# Power.net
KiCad netlist of a schematic drawn in Altium Designer
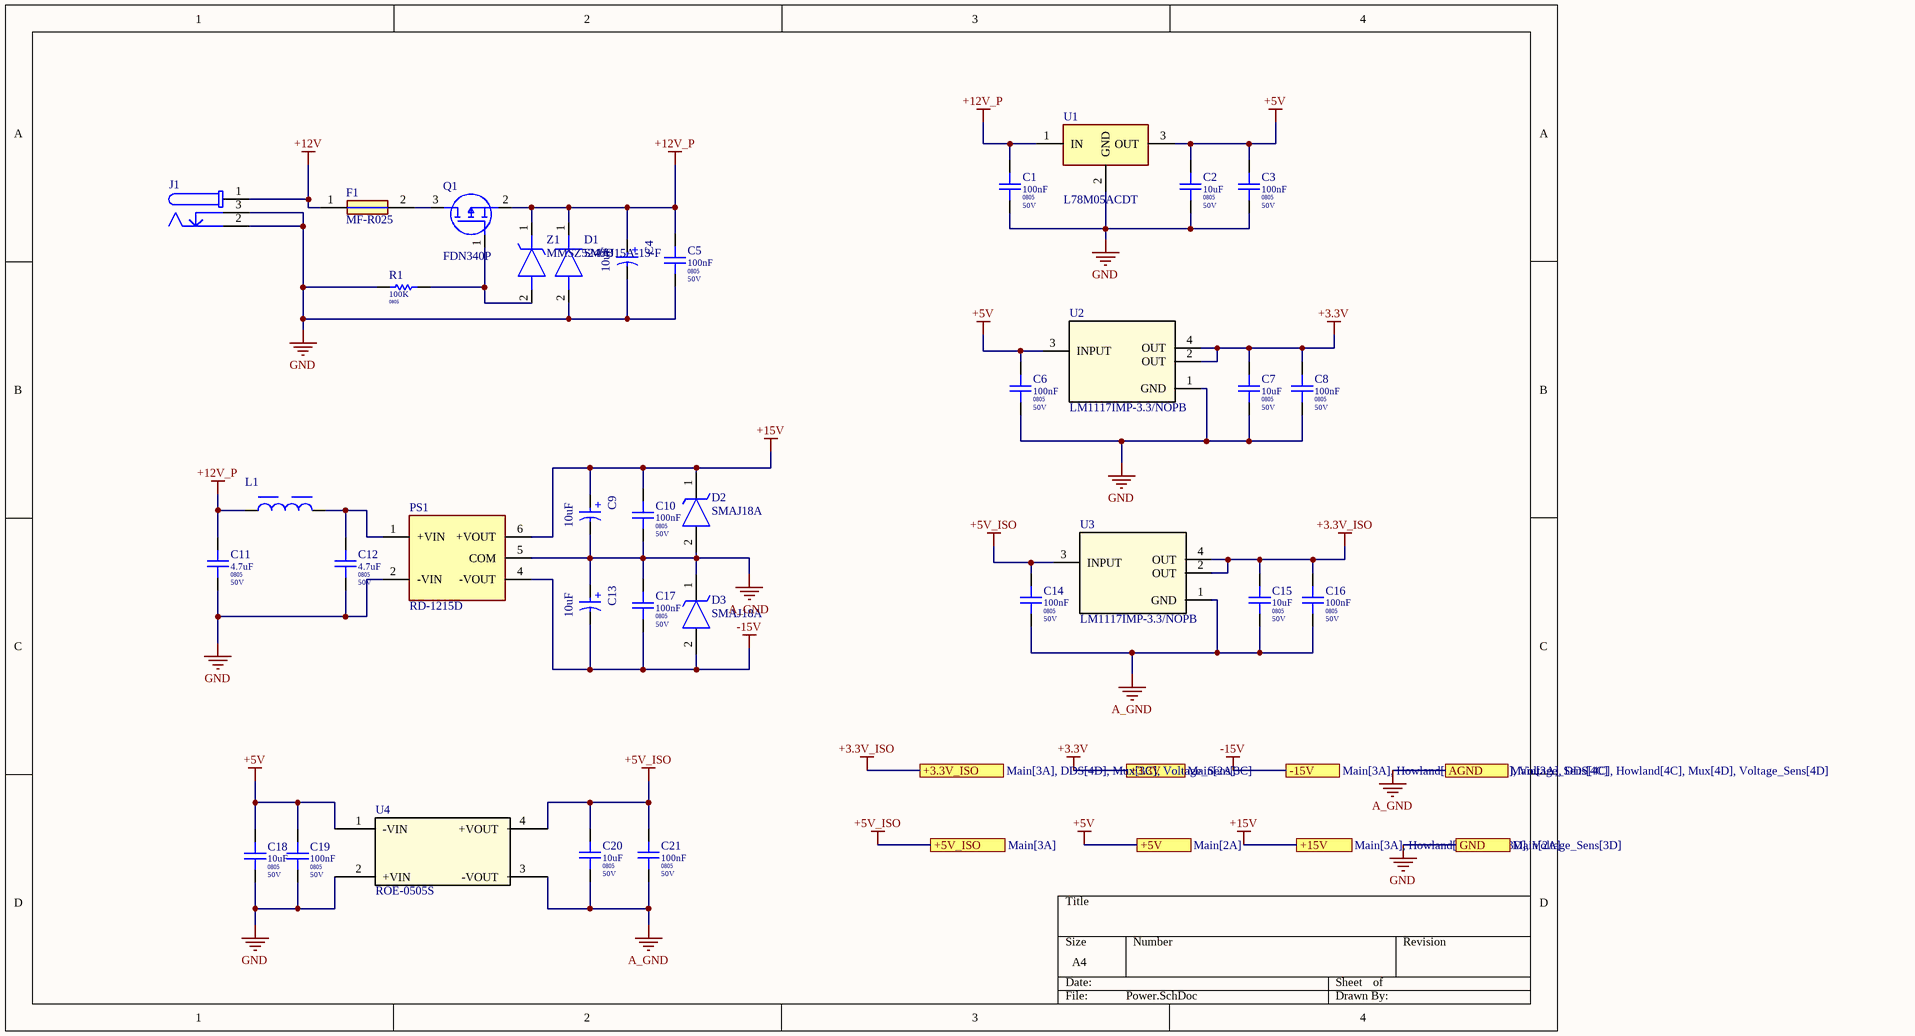
[diagram p0: Power.SchDoc]

(export (version "E")
  (design (tool "Eeschema 10.0.6"))
  (components
    (comp (ref "C1")
      (value "100nF")
      (footprint "CAPC 0805")
      (description "Capacitor Ceramic 100nF 50V 0805")
      (fields
        (field (name "TOLERANCE") "%10")
        (field (name "PACKAGE / CASE") "0805")
        (field (name "VOLTAGE") "50V")
        (field (name "PART NUMBER") "CAPC0572")
      )
      (libsource (lib "Aesk Database Library") (part "NPCapacitor"))
    )
    (comp (ref "C2")
      (value "10uF")
      (footprint "CAPC 0805")
      (description "Capacitor Ceramic 10uF 50V 0805")
      (fields
        (field (name "TOLERANCE") "%10")
        (field (name "PACKAGE / CASE") "0805")
        (field (name "VOLTAGE") "50V")
        (field (name "PART NUMBER") "CAPC0588")
      )
      (libsource (lib "Aesk Database Library") (part "NPCapacitor"))
    )
    (comp (ref "C3")
      (value "100nF")
      (footprint "CAPC 0805")
      (description "Capacitor Ceramic 100nF 50V 0805")
      (fields
        (field (name "TOLERANCE") "%10")
        (field (name "PACKAGE / CASE") "0805")
        (field (name "VOLTAGE") "50V")
        (field (name "PART NUMBER") "CAPC0572")
      )
      (libsource (lib "Aesk Database Library") (part "NPCapacitor"))
    )
    (comp (ref "C4")
      (value "10uF")
      (footprint "WCAP-ATG5_D5H11")
      (description "WCAP-ATG5 Aluminum Electrolytic Capacitor, Radial, THT, D5 x H11mm, 10µF, 35V")
      (fields
        (field (name "MANUFACTURER PART NUMBER") "860020572003")
        (field (name "MANUFACTURER") "Wurth Elektronik")
      )
      (libsource (lib "WE - Passive Components") (part "Capacitor_Polarized"))
    )
    (comp (ref "C5")
      (value "100nF")
      (footprint "CAPC 0805")
      (description "Capacitor Ceramic 100nF 50V 0805")
      (fields
        (field (name "TOLERANCE") "%10")
        (field (name "PACKAGE / CASE") "0805")
        (field (name "VOLTAGE") "50V")
        (field (name "PART NUMBER") "CAPC0572")
      )
      (libsource (lib "Aesk Database Library") (part "NPCapacitor"))
    )
    (comp (ref "C6")
      (value "100nF")
      (footprint "CAPC 0805")
      (description "Capacitor Ceramic 100nF 50V 0805")
      (fields
        (field (name "TOLERANCE") "%10")
        (field (name "PACKAGE / CASE") "0805")
        (field (name "VOLTAGE") "50V")
        (field (name "PART NUMBER") "CAPC0572")
      )
      (libsource (lib "Aesk Database Library") (part "NPCapacitor"))
    )
    (comp (ref "C7")
      (value "10uF")
      (footprint "CAPC 0805")
      (description "Capacitor Ceramic 10uF 50V 0805")
      (fields
        (field (name "TOLERANCE") "%10")
        (field (name "PACKAGE / CASE") "0805")
        (field (name "VOLTAGE") "50V")
        (field (name "PART NUMBER") "CAPC0588")
      )
      (libsource (lib "Aesk Database Library") (part "NPCapacitor"))
    )
    (comp (ref "C8")
      (value "100nF")
      (footprint "CAPC 0805")
      (description "Capacitor Ceramic 100nF 50V 0805")
      (fields
        (field (name "TOLERANCE") "%10")
        (field (name "PACKAGE / CASE") "0805")
        (field (name "VOLTAGE") "50V")
        (field (name "PART NUMBER") "CAPC0572")
      )
      (libsource (lib "Aesk Database Library") (part "NPCapacitor"))
    )
    (comp (ref "C9")
      (value "10uF")
      (footprint "WCAP-ATG5_D5H11")
      (description "WCAP-ATG5 Aluminum Electrolytic Capacitor, Radial, THT, D5 x H11mm, 10µF, 35V")
      (fields
        (field (name "MANUFACTURER PART NUMBER") "860020572003")
        (field (name "MANUFACTURER") "Wurth Elektronik")
      )
      (libsource (lib "WE - Passive Components") (part "Capacitor_Polarized"))
    )
    (comp (ref "C10")
      (value "100nF")
      (footprint "CAPC 0805")
      (description "Capacitor Ceramic 100nF 50V 0805")
      (fields
        (field (name "TOLERANCE") "%10")
        (field (name "PACKAGE / CASE") "0805")
        (field (name "VOLTAGE") "50V")
        (field (name "PART NUMBER") "CAPC0572")
      )
      (libsource (lib "Aesk Database Library") (part "NPCapacitor"))
    )
    (comp (ref "C11")
      (value "4.7uF")
      (footprint "CAPC 0805")
      (description "Capacitor Ceramic 4.7uF 50V 0805")
      (fields
        (field (name "TOLERANCE") "%10")
        (field (name "PACKAGE / CASE") "0805")
        (field (name "VOLTAGE") "50V")
        (field (name "PART NUMBER") "CAPC0584")
      )
      (libsource (lib "Aesk Database Library") (part "NPCapacitor"))
    )
    (comp (ref "C12")
      (value "4.7uF")
      (footprint "CAPC 0805")
      (description "Capacitor Ceramic 4.7uF 50V 0805")
      (fields
        (field (name "TOLERANCE") "%10")
        (field (name "PACKAGE / CASE") "0805")
        (field (name "VOLTAGE") "50V")
        (field (name "PART NUMBER") "CAPC0584")
      )
      (libsource (lib "Aesk Database Library") (part "NPCapacitor"))
    )
    (comp (ref "C13")
      (value "10uF")
      (footprint "WCAP-ATG5_D5H11")
      (description "WCAP-ATG5 Aluminum Electrolytic Capacitor, Radial, THT, D5 x H11mm, 10µF, 35V")
      (fields
        (field (name "MANUFACTURER PART NUMBER") "860020572003")
        (field (name "MANUFACTURER") "Wurth Elektronik")
      )
      (libsource (lib "WE - Passive Components") (part "Capacitor_Polarized"))
    )
    (comp (ref "C14")
      (value "100nF")
      (footprint "CAPC 0805")
      (description "Capacitor Ceramic 100nF 50V 0805")
      (fields
        (field (name "TOLERANCE") "%10")
        (field (name "PACKAGE / CASE") "0805")
        (field (name "VOLTAGE") "50V")
        (field (name "PART NUMBER") "CAPC0572")
      )
      (libsource (lib "Aesk Database Library") (part "NPCapacitor"))
    )
    (comp (ref "C15")
      (value "10uF")
      (footprint "CAPC 0805")
      (description "Capacitor Ceramic 10uF 50V 0805")
      (fields
        (field (name "TOLERANCE") "%10")
        (field (name "PACKAGE / CASE") "0805")
        (field (name "VOLTAGE") "50V")
        (field (name "PART NUMBER") "CAPC0588")
      )
      (libsource (lib "Aesk Database Library") (part "NPCapacitor"))
    )
    (comp (ref "C16")
      (value "100nF")
      (footprint "CAPC 0805")
      (description "Capacitor Ceramic 100nF 50V 0805")
      (fields
        (field (name "TOLERANCE") "%10")
        (field (name "PACKAGE / CASE") "0805")
        (field (name "VOLTAGE") "50V")
        (field (name "PART NUMBER") "CAPC0572")
      )
      (libsource (lib "Aesk Database Library") (part "NPCapacitor"))
    )
    (comp (ref "C17")
      (value "100nF")
      (footprint "CAPC 0805")
      (description "Capacitor Ceramic 100nF 50V 0805")
      (fields
        (field (name "TOLERANCE") "%10")
        (field (name "PACKAGE / CASE") "0805")
        (field (name "VOLTAGE") "50V")
        (field (name "PART NUMBER") "CAPC0572")
      )
      (libsource (lib "Aesk Database Library") (part "NPCapacitor"))
    )
    (comp (ref "C18")
      (value "10uF")
      (footprint "CAPC 0805")
      (description "Capacitor Ceramic 10uF 50V 0805")
      (fields
        (field (name "TOLERANCE") "%10")
        (field (name "PACKAGE / CASE") "0805")
        (field (name "VOLTAGE") "50V")
        (field (name "PART NUMBER") "CAPC0588")
      )
      (libsource (lib "Aesk Database Library") (part "NPCapacitor"))
    )
    (comp (ref "C19")
      (value "100nF")
      (footprint "CAPC 0805")
      (description "Capacitor Ceramic 100nF 50V 0805")
      (fields
        (field (name "TOLERANCE") "%10")
        (field (name "PACKAGE / CASE") "0805")
        (field (name "VOLTAGE") "50V")
        (field (name "PART NUMBER") "CAPC0572")
      )
      (libsource (lib "Aesk Database Library") (part "NPCapacitor"))
    )
    (comp (ref "C20")
      (value "10uF")
      (footprint "CAPC 0805")
      (description "Capacitor Ceramic 10uF 50V 0805")
      (fields
        (field (name "TOLERANCE") "%10")
        (field (name "PACKAGE / CASE") "0805")
        (field (name "VOLTAGE") "50V")
        (field (name "PART NUMBER") "CAPC0588")
      )
      (libsource (lib "Aesk Database Library") (part "NPCapacitor"))
    )
    (comp (ref "C21")
      (value "100nF")
      (footprint "CAPC 0805")
      (description "Capacitor Ceramic 100nF 50V 0805")
      (fields
        (field (name "TOLERANCE") "%10")
        (field (name "PACKAGE / CASE") "0805")
        (field (name "VOLTAGE") "50V")
        (field (name "PART NUMBER") "CAPC0572")
      )
      (libsource (lib "Aesk Database Library") (part "NPCapacitor"))
    )
    (comp (ref "D1")
      (value "SMAJ15A-13-F")
      (footprint "SamacSys:DIOM5226X240N")
      (description "Diode")
      (fields (field (name "MOUSER PART NUMBER") "621-SMAJ15A-13-F"))
      (libsource (lib "Schlib1") (part "SMAJ15A-13-F"))
    )
    (comp (ref "D2")
      (value "SMAJ18A")
      (footprint "SamacSys:DIOM5026X229N")
      (description "TVS Diode (Uni-directional)")
      (fields (field (name "MOUSER PART NUMBER") "576-SMAJ18A"))
      (libsource (lib "Schlib1") (part "SMAJ18A"))
    )
    (comp (ref "D3")
      (value "SMAJ18A")
      (footprint "SamacSys:DIOM5026X229N")
      (description "TVS Diode (Uni-directional)")
      (fields (field (name "MOUSER PART NUMBER") "576-SMAJ18A"))
      (libsource (lib "Schlib1") (part "SMAJ18A"))
    )
    (comp (ref "F1")
      (value "MF-R025")
      (footprint "SamacSys:MFR025")
      (description "Fuse")
      (fields (field (name "MOUSER PART NUMBER") "652-MFR025"))
      (libsource (lib "Schlib1") (part "MF-R025"))
    )
    (comp (ref "J1")
      (value "694106301002")
      (footprint "694106301002")
      (description "WR-DC Power Jack, THT, Right Angled, Center Pin 2mm, 5A, 30V (DC)")
      (fields (field (name "MANUFACTURER") "Wurth Elektronik"))
      (libsource (lib "WE - Electromechanical Components") (part "DC Power Jack_Switch On Pin 2"))
    )
    (comp (ref "L1")
      (value "10uH, 0.74A")
      (footprint "WE-TPC_3816")
      (description "WE-TPC SMT Tiny Power Inductor, size 3816, 10uH, 0.74A, 185mOhm")
      (fields
        (field (name "MANUFACTURER PART NUMBER") "744031100")
        (field (name "MANUFACTURER") "Wurth Elektronik")
      )
      (libsource (lib "WE - Passive Components") (part "Inductor - 3"))
    )
    (comp (ref "PS1")
      (value "RD-1215D")
      (footprint "SamacSys:RD1215D")
      (description "Power Supply")
      (fields (field (name "MOUSER PART NUMBER") "919-RD-1215D"))
      (libsource (lib "Schlib1") (part "RD-1215D"))
    )
    (comp (ref "Q1")
      (value "FDN340P")
      (footprint "SamacSys:SOT95P237X112-3N")
      (description "MOSFET (P-Channel)")
      (fields (field (name "MOUSER PART NUMBER") "512-FDN340P"))
      (libsource (lib "Schlib1") (part "FDN340P"))
    )
    (comp (ref "R1")
      (value "100K")
      (footprint "RESC 0805")
      (description "100K 0805")
      (fields
        (field (name "TOLERANCE") "%5")
        (field (name "POWER") "1/10W")
        (field (name "PACKAGE / CASE") "0805")
      )
      (libsource (lib "Aesk Database Library") (part "Resistor"))
    )
    (comp (ref "U1")
      (value "L78M05ACDT")
      (footprint "SamacSys:L78M05ACDT")
      (description "Integrated Circuit")
      (fields (field (name "MOUSER PART NUMBER") "511-L78M05ACDT"))
      (libsource (lib "Schlib1") (part "L78M05ACDT"))
    )
    (comp (ref "U2")
      (value "LM1117IMP-3.3/NOPB")
      (footprint "DCY0004A_M")
      (description "800-mA 15-V linear voltage regulator 4-SOT-223 -40 to 125")
      (fields (field (name "COPYRIGHT") "Copyright (C) 2025 Ultra Librarian. All rights reserved."))
      (libsource (lib "Schlib1") (part "LM1117IMP-3.3NOPB"))
    )
    (comp (ref "U3")
      (value "LM1117IMP-3.3/NOPB")
      (footprint "DCY0004A_M")
      (description "800-mA 15-V linear voltage regulator 4-SOT-223 -40 to 125")
      (fields (field (name "COPYRIGHT") "Copyright (C) 2025 Ultra Librarian. All rights reserved."))
      (libsource (lib "Schlib1") (part "LM1117IMP-3.3NOPB"))
    )
    (comp (ref "U4")
      (value "ROE-0505S")
      (footprint "ROE_RCP")
      (description "Description")
      (fields (field (name "COPYRIGHT") "Copyright (C) 2026 Ultra Librarian. All rights reserved."))
      (libsource (lib "Schlib1") (part "ROE-0505S"))
    )
    (comp (ref "Z1")
      (value "MMSZ5240B")
      (footprint "SamacSys:SOD3816X128N")
      (description "Zener Diode")
      (fields (field (name "MOUSER PART NUMBER") "512-MMSZ5240B"))
      (libsource (lib "Schlib1") (part "MMSZ5240B"))
    )
  )
  (nets
    (net (code "1") (name "+3.3V") (class "Default")
      (node (ref "C7") (pin "2") (pinfunction "2_2") (pintype "passive"))
      (node (ref "C8") (pin "2") (pinfunction "2_2") (pintype "passive"))
      (node (ref "U2") (pin "2") (pinfunction "OUT_2") (pintype "power_in"))
      (node (ref "U2") (pin "4") (pinfunction "OUT_4") (pintype "power_in"))
    )
    (net (code "2") (name "+3.3V_ISO") (class "Default")
      (node (ref "C15") (pin "2") (pinfunction "2_2") (pintype "passive"))
      (node (ref "C16") (pin "2") (pinfunction "2_2") (pintype "passive"))
      (node (ref "U3") (pin "2") (pinfunction "OUT_2") (pintype "power_in"))
      (node (ref "U3") (pin "4") (pinfunction "OUT_4") (pintype "power_in"))
    )
    (net (code "3") (name "+5V") (class "Default")
      (node (ref "C18") (pin "2") (pinfunction "2_2") (pintype "passive"))
      (node (ref "C19") (pin "2") (pinfunction "2_2") (pintype "passive"))
      (node (ref "C2") (pin "2") (pinfunction "2_2") (pintype "passive"))
      (node (ref "C3") (pin "2") (pinfunction "2_2") (pintype "passive"))
      (node (ref "C6") (pin "2") (pinfunction "2_2") (pintype "passive"))
      (node (ref "U1") (pin "3") (pinfunction "OUT_3") (pintype "power_in"))
      (node (ref "U2") (pin "3") (pinfunction "INPUT_3") (pintype "power_in"))
      (node (ref "U4") (pin "1") (pinfunction "-VIN_1") (pintype "power_in"))
    )
    (net (code "4") (name "+5V_ISO") (class "Default")
      (node (ref "C14") (pin "2") (pinfunction "2_2") (pintype "passive"))
      (node (ref "C20") (pin "2") (pinfunction "2_2") (pintype "passive"))
      (node (ref "C21") (pin "2") (pinfunction "2_2") (pintype "passive"))
      (node (ref "U3") (pin "3") (pinfunction "INPUT_3") (pintype "power_in"))
      (node (ref "U4") (pin "4") (pinfunction "+VOUT_4") (pintype "power_in"))
    )
    (net (code "5") (name "+12V") (class "Default")
      (node (ref "F1") (pin "1") (pinfunction "1_1") (pintype "passive"))
      (node (ref "J1") (pin "1") (pinfunction "1_1") (pintype "passive"))
    )
    (net (code "6") (name "+12V_P") (class "Default")
      (node (ref "C1") (pin "2") (pinfunction "2_2") (pintype "passive"))
      (node (ref "C11") (pin "2") (pinfunction "2_2") (pintype "passive"))
      (node (ref "C4") (pin "1") (pinfunction "P_1") (pintype "passive"))
      (node (ref "C5") (pin "2") (pinfunction "2_2") (pintype "passive"))
      (node (ref "D1") (pin "1") (pinfunction "K_1") (pintype "passive"))
      (node (ref "L1") (pin "1") (pinfunction "1_1") (pintype "passive"))
      (node (ref "Q1") (pin "2") (pinfunction "S_2") (pintype "passive"))
      (node (ref "U1") (pin "1") (pinfunction "IN_1") (pintype "power_in"))
      (node (ref "Z1") (pin "1") (pinfunction "K_1") (pintype "passive"))
    )
    (net (code "7") (name "+15V") (class "Default")
      (node (ref "C10") (pin "2") (pinfunction "2_2") (pintype "passive"))
      (node (ref "C9") (pin "1") (pinfunction "P_1") (pintype "passive"))
      (node (ref "D2") (pin "1") (pinfunction "K_1") (pintype "passive"))
      (node (ref "PS1") (pin "6") (pinfunction "+VOUT_6") (pintype "passive"))
    )
    (net (code "8") (name "-15V") (class "Default")
      (node (ref "C13") (pin "2") (pinfunction "N_2") (pintype "passive"))
      (node (ref "C17") (pin "1") (pinfunction "1_1") (pintype "passive"))
      (node (ref "D3") (pin "2") (pinfunction "A_2") (pintype "passive"))
      (node (ref "PS1") (pin "4") (pinfunction "-VOUT_4") (pintype "passive"))
    )
    (net (code "9") (name "A_GND") (class "Default")
      (node (ref "C10") (pin "1") (pinfunction "1_1") (pintype "passive"))
      (node (ref "C13") (pin "1") (pinfunction "P_1") (pintype "passive"))
      (node (ref "C14") (pin "1") (pinfunction "1_1") (pintype "passive"))
      (node (ref "C15") (pin "1") (pinfunction "1_1") (pintype "passive"))
      (node (ref "C16") (pin "1") (pinfunction "1_1") (pintype "passive"))
      (node (ref "C17") (pin "2") (pinfunction "2_2") (pintype "passive"))
      (node (ref "C20") (pin "1") (pinfunction "1_1") (pintype "passive"))
      (node (ref "C21") (pin "1") (pinfunction "1_1") (pintype "passive"))
      (node (ref "C9") (pin "2") (pinfunction "N_2") (pintype "passive"))
      (node (ref "D2") (pin "2") (pinfunction "A_2") (pintype "passive"))
      (node (ref "D3") (pin "1") (pinfunction "K_1") (pintype "passive"))
      (node (ref "PS1") (pin "5") (pinfunction "COM_5") (pintype "passive"))
      (node (ref "U3") (pin "1") (pinfunction "GND_1") (pintype "power_in"))
      (node (ref "U4") (pin "3") (pinfunction "-VOUT_3") (pintype "power_in"))
    )
    (net (code "10") (name "GND") (class "Default")
      (node (ref "C1") (pin "1") (pinfunction "1_1") (pintype "passive"))
      (node (ref "C11") (pin "1") (pinfunction "1_1") (pintype "passive"))
      (node (ref "C12") (pin "1") (pinfunction "1_1") (pintype "passive"))
      (node (ref "C18") (pin "1") (pinfunction "1_1") (pintype "passive"))
      (node (ref "C19") (pin "1") (pinfunction "1_1") (pintype "passive"))
      (node (ref "C2") (pin "1") (pinfunction "1_1") (pintype "passive"))
      (node (ref "C3") (pin "1") (pinfunction "1_1") (pintype "passive"))
      (node (ref "C4") (pin "2") (pinfunction "N_2") (pintype "passive"))
      (node (ref "C5") (pin "1") (pinfunction "1_1") (pintype "passive"))
      (node (ref "C6") (pin "1") (pinfunction "1_1") (pintype "passive"))
      (node (ref "C7") (pin "1") (pinfunction "1_1") (pintype "passive"))
      (node (ref "C8") (pin "1") (pinfunction "1_1") (pintype "passive"))
      (node (ref "D1") (pin "2") (pinfunction "A_2") (pintype "passive"))
      (node (ref "J1") (pin "2") (pinfunction "2_2") (pintype "passive"))
      (node (ref "J1") (pin "3") (pinfunction "3_3") (pintype "passive"))
      (node (ref "PS1") (pin "2") (pinfunction "-VIN_2") (pintype "passive"))
      (node (ref "R1") (pin "2") (pinfunction "2_2") (pintype "passive"))
      (node (ref "U1") (pin "2") (pinfunction "GND_2") (pintype "power_in"))
      (node (ref "U2") (pin "1") (pinfunction "GND_1") (pintype "power_in"))
      (node (ref "U4") (pin "2") (pinfunction "+VIN_2") (pintype "power_in"))
    )
    (net (code "11") (name "Net-(PS1-+VIN)") (class "Default")
      (node (ref "C12") (pin "2") (pinfunction "2_2") (pintype "passive"))
      (node (ref "L1") (pin "2") (pinfunction "2_2") (pintype "passive"))
      (node (ref "PS1") (pin "1") (pinfunction "+VIN_1") (pintype "passive"))
    )
    (net (code "12") (name "Net-(Q1-D)") (class "Default")
      (node (ref "F1") (pin "2") (pinfunction "2_2") (pintype "passive"))
      (node (ref "Q1") (pin "3") (pinfunction "D_3") (pintype "passive"))
    )
    (net (code "13") (name "Net-(Q1-G)") (class "Default")
      (node (ref "Q1") (pin "1") (pinfunction "G_1") (pintype "passive"))
      (node (ref "R1") (pin "1") (pinfunction "1_1") (pintype "passive"))
      (node (ref "Z1") (pin "2") (pinfunction "A_2") (pintype "passive"))
    )
  )
)
